# Wireless_IMU_v1_0.net
KiCad netlist of a schematic drawn in EAGLE
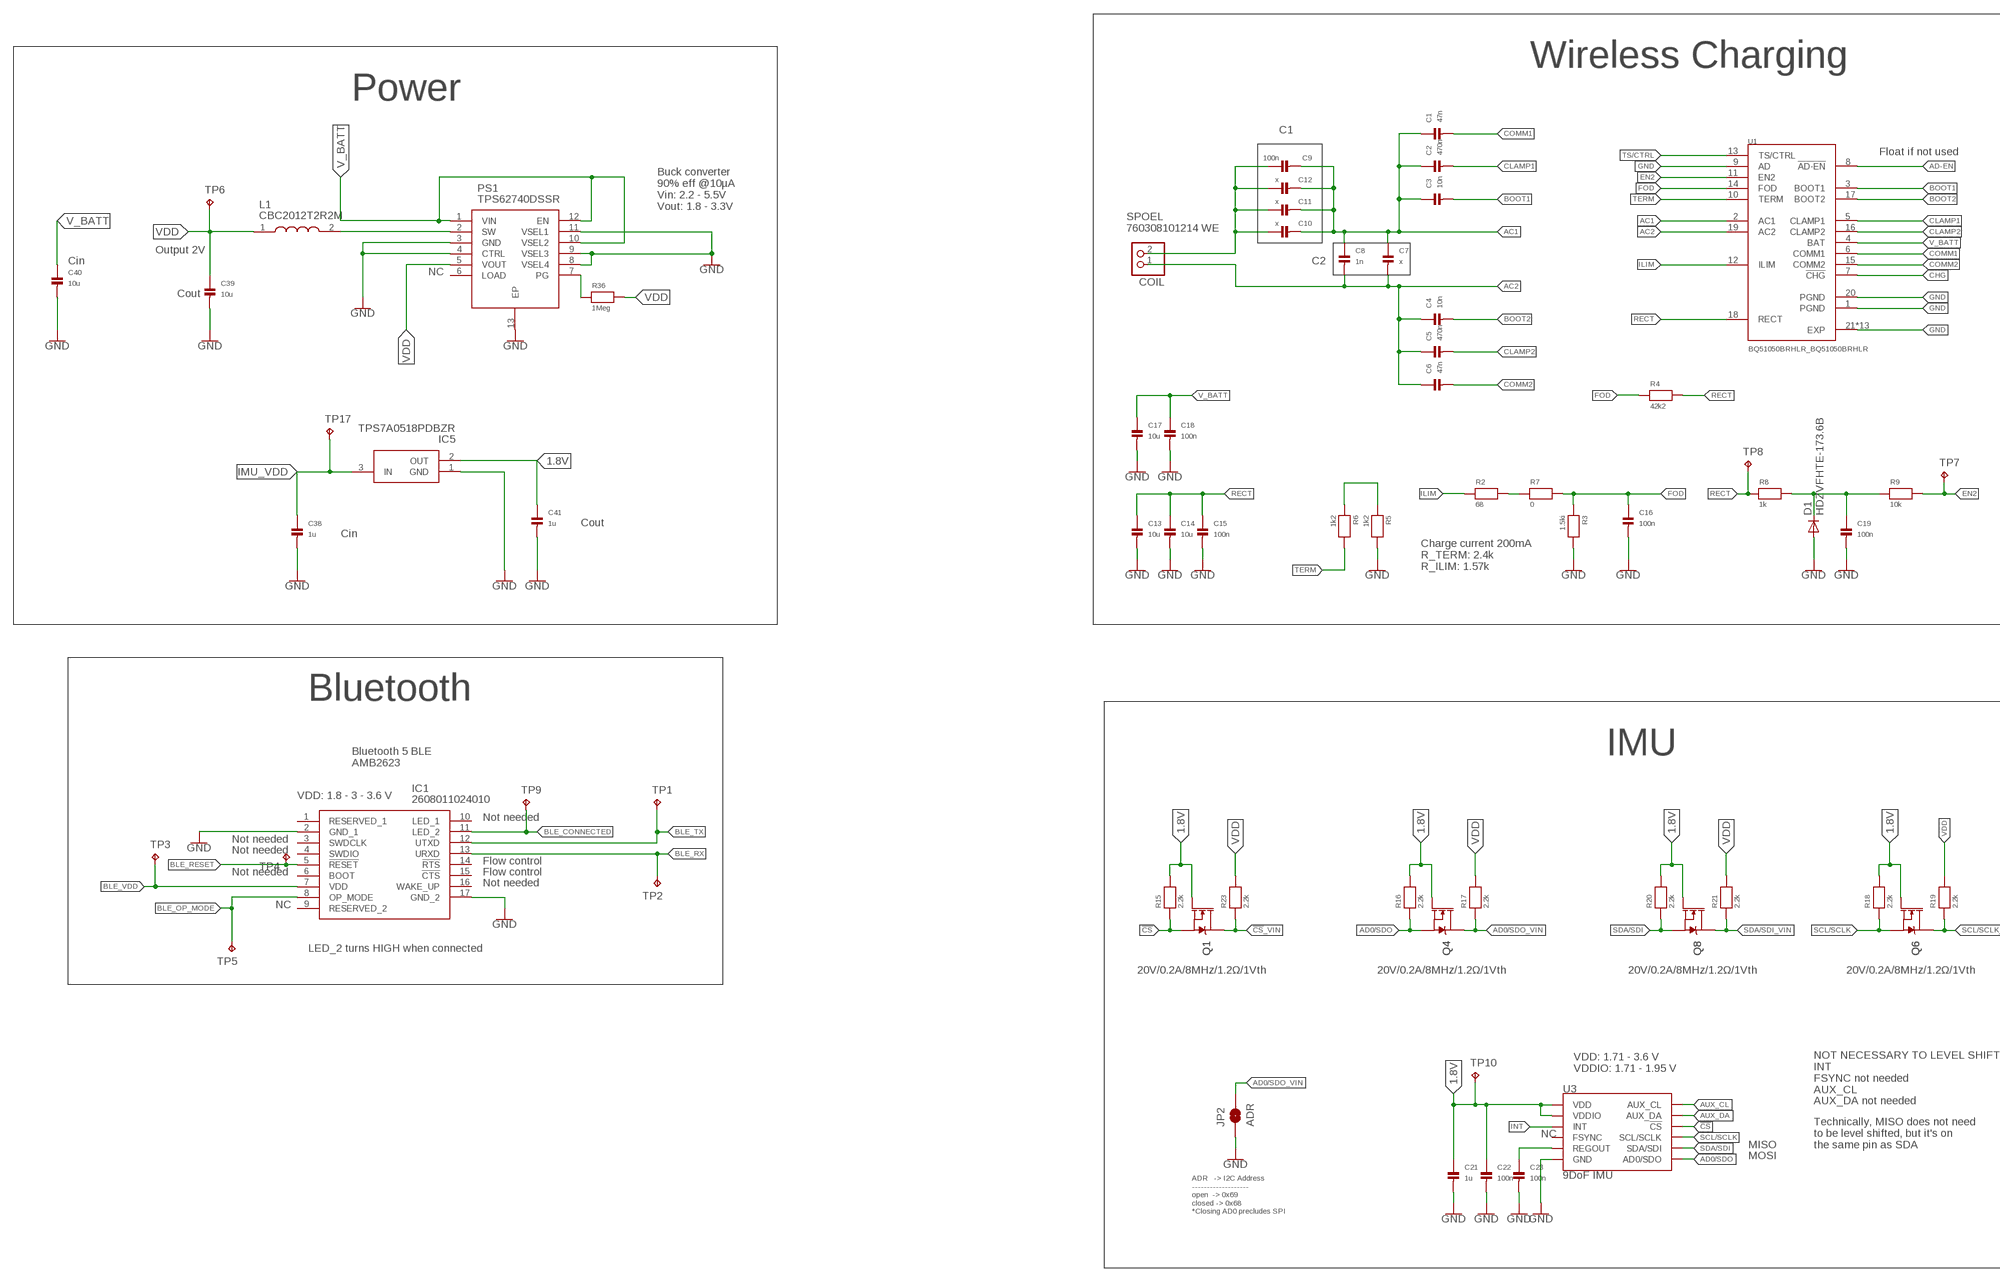
[diagram p0: schematic, sheet 1, part 1 of 2]
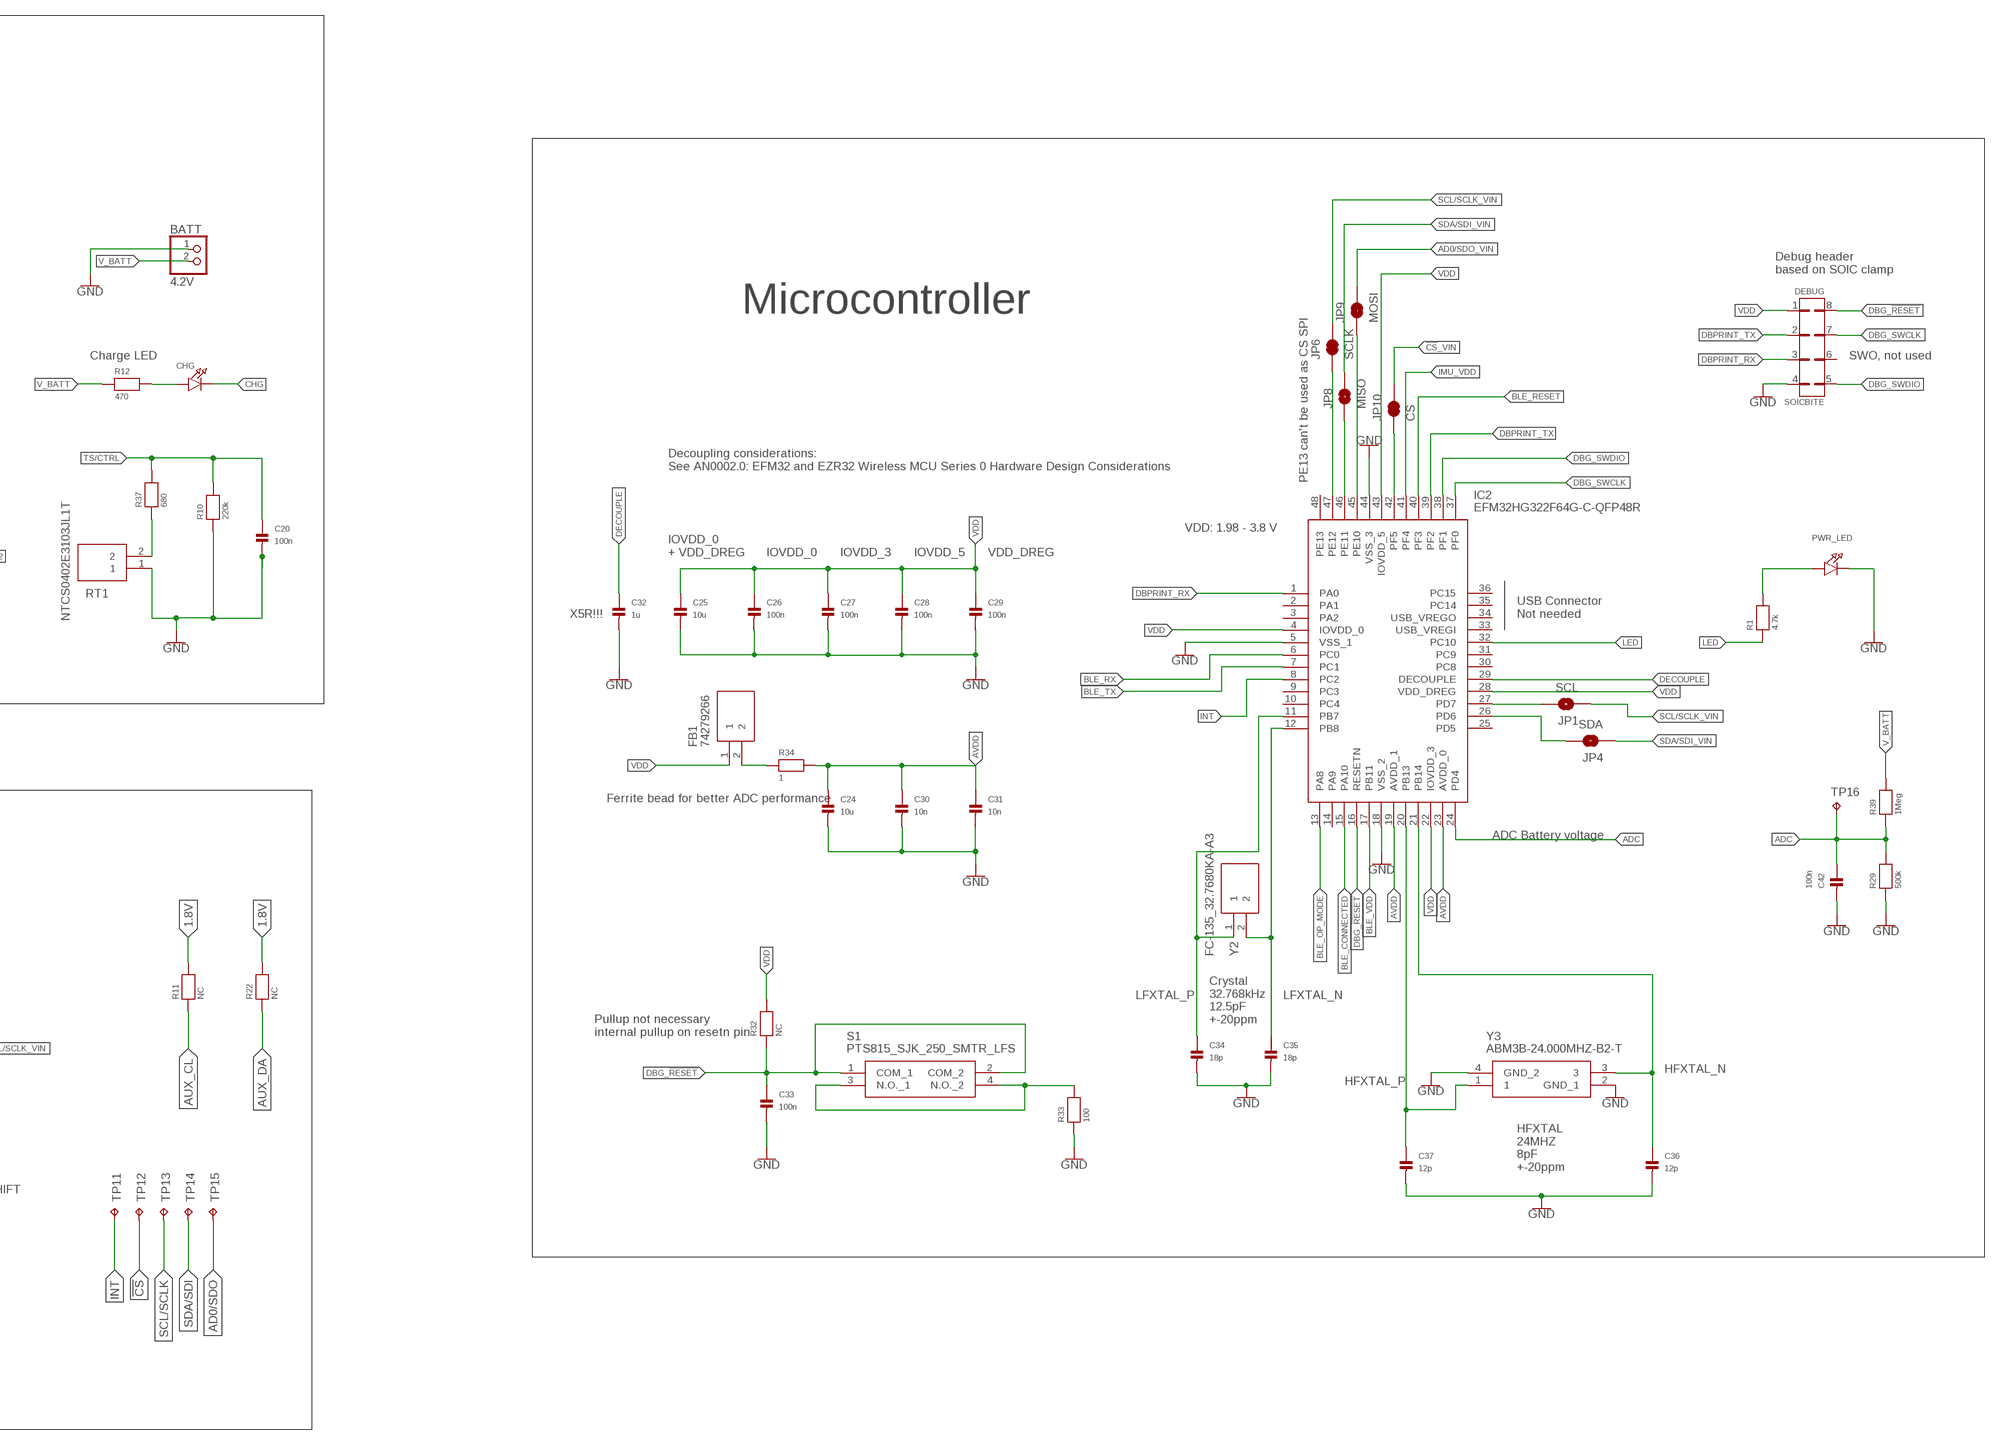
[diagram p1: schematic, sheet 1, part 2 of 2]

(export (version "E")
  (design (tool "Eeschema 10.0.6"))
  (components
    (comp (ref "BATT")
      (value "4.2V")
      (footprint "eagle-import:1X02")
      (libsource (lib "eagle-import") (part "pinhead_325_PINHD-1X2"))
    )
    (comp (ref "C1")
      (value "47n")
      (footprint "eagle-import:0603")
      (libsource (lib "eagle-import") (part "CAP_CERAMIC0603"))
    )
    (comp (ref "C2")
      (value "470n")
      (footprint "eagle-import:0603")
      (libsource (lib "eagle-import") (part "CAP_CERAMIC0603"))
    )
    (comp (ref "C3")
      (value "10n")
      (footprint "eagle-import:0603")
      (libsource (lib "eagle-import") (part "CAP_CERAMIC0603"))
    )
    (comp (ref "C4")
      (value "10n")
      (footprint "eagle-import:0603")
      (libsource (lib "eagle-import") (part "CAP_CERAMIC0603"))
    )
    (comp (ref "C5")
      (value "470n")
      (footprint "eagle-import:0603")
      (libsource (lib "eagle-import") (part "CAP_CERAMIC0603"))
    )
    (comp (ref "C6")
      (value "47n")
      (footprint "eagle-import:0603")
      (libsource (lib "eagle-import") (part "CAP_CERAMIC0603"))
    )
    (comp (ref "C7")
      (value "x")
      (footprint "eagle-import:0603")
      (libsource (lib "eagle-import") (part "CAP_CERAMIC0603"))
    )
    (comp (ref "C8")
      (value "1n")
      (footprint "eagle-import:0603")
      (libsource (lib "eagle-import") (part "CAP_CERAMIC0603"))
    )
    (comp (ref "C9")
      (value "100n")
      (footprint "eagle-import:0603")
      (libsource (lib "eagle-import") (part "CAP_CERAMIC0603"))
    )
    (comp (ref "C10")
      (value "x")
      (footprint "eagle-import:0603")
      (libsource (lib "eagle-import") (part "CAP_CERAMIC0603"))
    )
    (comp (ref "C11")
      (value "x")
      (footprint "eagle-import:0603")
      (libsource (lib "eagle-import") (part "CAP_CERAMIC0603"))
    )
    (comp (ref "C12")
      (value "x")
      (footprint "eagle-import:0603")
      (libsource (lib "eagle-import") (part "CAP_CERAMIC0603"))
    )
    (comp (ref "C13")
      (value "10u")
      (footprint "eagle-import:0603")
      (libsource (lib "eagle-import") (part "CAP_CERAMIC0603"))
    )
    (comp (ref "C14")
      (value "10u")
      (footprint "eagle-import:0603")
      (libsource (lib "eagle-import") (part "CAP_CERAMIC0603"))
    )
    (comp (ref "C15")
      (value "100n")
      (footprint "eagle-import:0603")
      (libsource (lib "eagle-import") (part "CAP_CERAMIC0603"))
    )
    (comp (ref "C16")
      (value "100n")
      (footprint "eagle-import:0603")
      (libsource (lib "eagle-import") (part "CAP_CERAMIC0603"))
    )
    (comp (ref "C17")
      (value "10u")
      (footprint "eagle-import:0603")
      (libsource (lib "eagle-import") (part "CAP_CERAMIC0603"))
    )
    (comp (ref "C18")
      (value "100n")
      (footprint "eagle-import:0603")
      (libsource (lib "eagle-import") (part "CAP_CERAMIC0603"))
    )
    (comp (ref "C19")
      (value "100n")
      (footprint "eagle-import:0603")
      (libsource (lib "eagle-import") (part "CAP_CERAMIC0603"))
    )
    (comp (ref "C20")
      (value "100n")
      (footprint "eagle-import:0603")
      (libsource (lib "eagle-import") (part "CAP_CERAMIC0603"))
    )
    (comp (ref "C21")
      (value "1u")
      (footprint "eagle-import:0603")
      (libsource (lib "eagle-import") (part "CAP_CERAMIC0603"))
    )
    (comp (ref "C22")
      (value "100n")
      (footprint "eagle-import:0603")
      (libsource (lib "eagle-import") (part "CAP_CERAMIC0603"))
    )
    (comp (ref "C23")
      (value "100n")
      (footprint "eagle-import:0603")
      (libsource (lib "eagle-import") (part "CAP_CERAMIC0603"))
    )
    (comp (ref "C24")
      (value "10u")
      (footprint "eagle-import:0603")
      (libsource (lib "eagle-import") (part "CAP_CERAMIC0603"))
    )
    (comp (ref "C25")
      (value "10u")
      (footprint "eagle-import:0603")
      (libsource (lib "eagle-import") (part "CAP_CERAMIC0603"))
    )
    (comp (ref "C26")
      (value "100n")
      (footprint "eagle-import:0603")
      (libsource (lib "eagle-import") (part "CAP_CERAMIC0603"))
    )
    (comp (ref "C27")
      (value "100n")
      (footprint "eagle-import:0603")
      (libsource (lib "eagle-import") (part "CAP_CERAMIC0603"))
    )
    (comp (ref "C28")
      (value "100n")
      (footprint "eagle-import:0603")
      (libsource (lib "eagle-import") (part "CAP_CERAMIC0603"))
    )
    (comp (ref "C29")
      (value "100n")
      (footprint "eagle-import:0603")
      (libsource (lib "eagle-import") (part "CAP_CERAMIC0603"))
    )
    (comp (ref "C30")
      (value "10n")
      (footprint "eagle-import:0603")
      (libsource (lib "eagle-import") (part "CAP_CERAMIC0603"))
    )
    (comp (ref "C31")
      (value "10n")
      (footprint "eagle-import:0603")
      (libsource (lib "eagle-import") (part "CAP_CERAMIC0603"))
    )
    (comp (ref "C32")
      (value "1u")
      (footprint "eagle-import:0603")
      (libsource (lib "eagle-import") (part "CAP_CERAMIC0603"))
    )
    (comp (ref "C33")
      (value "100n")
      (footprint "eagle-import:0603")
      (libsource (lib "eagle-import") (part "CAP_CERAMIC0603"))
    )
    (comp (ref "C34")
      (value "18p")
      (footprint "eagle-import:0603")
      (libsource (lib "eagle-import") (part "CAP_CERAMIC0603"))
    )
    (comp (ref "C35")
      (value "18p")
      (footprint "eagle-import:0603")
      (libsource (lib "eagle-import") (part "CAP_CERAMIC0603"))
    )
    (comp (ref "C36")
      (value "12p")
      (footprint "eagle-import:0603")
      (libsource (lib "eagle-import") (part "CAP_CERAMIC0603"))
    )
    (comp (ref "C37")
      (value "12p")
      (footprint "eagle-import:0603")
      (libsource (lib "eagle-import") (part "CAP_CERAMIC0603"))
    )
    (comp (ref "C38")
      (value "1u")
      (footprint "eagle-import:0603")
      (libsource (lib "eagle-import") (part "CAP_CERAMIC0603"))
    )
    (comp (ref "C39")
      (value "10u")
      (footprint "eagle-import:0603")
      (libsource (lib "eagle-import") (part "CAP_CERAMIC0603"))
    )
    (comp (ref "C40")
      (value "10u")
      (footprint "eagle-import:0603")
      (libsource (lib "eagle-import") (part "CAP_CERAMIC0603"))
    )
    (comp (ref "C41")
      (value "1u")
      (footprint "eagle-import:0603")
      (libsource (lib "eagle-import") (part "CAP_CERAMIC0603"))
    )
    (comp (ref "C42")
      (value "100n")
      (footprint "eagle-import:0603")
      (libsource (lib "eagle-import") (part "CAP_CERAMIC0603"))
    )
    (comp (ref "CHG")
      (value "LED0805")
      (footprint "eagle-import:CHIPLED_0805")
      (libsource (lib "eagle-import") (part "LED0805"))
    )
    (comp (ref "COIL")
      (value "PINHD-1X2")
      (footprint "eagle-import:1X02")
      (libsource (lib "eagle-import") (part "PINHD-1X2"))
    )
    (comp (ref "D1")
      (value "HDZVFHTE-173.6B")
      (footprint "eagle-import:SOD323-W")
      (libsource (lib "eagle-import") (part "DIODE-SOD323-W"))
    )
    (comp (ref "DEBUG")
      (value "SOICBITE")
      (footprint "eagle-import:SOICBITE")
      (libsource (lib "eagle-import") (part "SOICBITE"))
    )
    (comp (ref "FB1")
      (value "74279266")
      (footprint "eagle-import:BEADC1608X100N")
      (fields (field (name "MOUSER_PART_NUMBER") "710-74279266"))
      (libsource (lib "eagle-import") (part "74279266"))
    )
    (comp (ref "IC1")
      (value "2608011024010")
      (footprint "eagle-import:2608011024010")
      (fields (field (name "MOUSER_PART_NUMBER") "710-2608011024010"))
      (libsource (lib "eagle-import") (part "2608011024010"))
    )
    (comp (ref "IC2")
      (value "EFM32HG322F64G-C-QFP48R")
      (footprint "eagle-import:QFP50P900X900X120-48N")
      (fields (field (name "MOUSER_PART_NUMBER") "634-HG322F64GCQFP48R"))
      (libsource (lib "eagle-import") (part "EFM32HG322F64G-C-QFP48R"))
    )
    (comp (ref "IC5")
      (value "TPS7A0518PDBZR")
      (footprint "eagle-import:SOT95P237X112-3N")
      (fields (field (name "MOUSER_PART_NUMBER") "595-TPS7A0518PDBZR"))
      (libsource (lib "eagle-import") (part "TPS7A0518PDBZR"))
    )
    (comp (ref "JP1")
      (value "SCL")
      (footprint "eagle-import:SMT-JUMPER_2_NO_SILK")
      (libsource (lib "eagle-import") (part "JUMPER-SMT_2_NO_SILK"))
    )
    (comp (ref "JP2")
      (value "ADR")
      (footprint "eagle-import:SMT-JUMPER_2_NO_SILK")
      (libsource (lib "eagle-import") (part "JUMPER-SMT_2_NO_SILK"))
    )
    (comp (ref "JP4")
      (value "SDA")
      (footprint "eagle-import:SMT-JUMPER_2_NO_SILK")
      (libsource (lib "eagle-import") (part "JUMPER-SMT_2_NO_SILK"))
    )
    (comp (ref "JP6")
      (value "SCLK")
      (footprint "eagle-import:SMT-JUMPER_2_NC_TRACE_SILK")
      (libsource (lib "eagle-import") (part "JUMPER-SMT_2_NC_TRACE_SILK"))
    )
    (comp (ref "JP8")
      (value "MISO")
      (footprint "eagle-import:SMT-JUMPER_2_NC_TRACE_SILK")
      (libsource (lib "eagle-import") (part "JUMPER-SMT_2_NC_TRACE_SILK"))
    )
    (comp (ref "JP9")
      (value "MOSI")
      (footprint "eagle-import:SMT-JUMPER_2_NC_TRACE_SILK")
      (libsource (lib "eagle-import") (part "JUMPER-SMT_2_NC_TRACE_SILK"))
    )
    (comp (ref "JP10")
      (value "CS")
      (footprint "eagle-import:SMT-JUMPER_2_NC_TRACE_SILK")
      (libsource (lib "eagle-import") (part "JUMPER-SMT_2_NC_TRACE_SILK"))
    )
    (comp (ref "L1")
      (value "CBC2012T2R2M")
      (footprint "eagle-import:INDC2012X145N")
      (fields (field (name "MOUSER_PART_NUMBER") "963-CBC2012T2R2M"))
      (libsource (lib "eagle-import") (part "CBC2012T2R2M"))
    )
    (comp (ref "PS1")
      (value "TPS62740DSSR")
      (footprint "eagle-import:SON50P200X300X80-13N")
      (fields (field (name "MOUSER_PART_NUMBER") "595-TPS62740DSSR"))
      (libsource (lib "eagle-import") (part "TPS62740DSSR"))
    )
    (comp (ref "PWR_LED")
      (value "LED0805")
      (footprint "eagle-import:CHIPLED_0805")
      (libsource (lib "eagle-import") (part "LED0805"))
    )
    (comp (ref "Q1")
      (value "20V/0.2A/8MHz/1.2Ω/1Vth")
      (footprint "eagle-import:SOT-416FL")
      (libsource (lib "eagle-import") (part "MOSFET-NCH-RE1C002UN"))
    )
    (comp (ref "Q4")
      (value "20V/0.2A/8MHz/1.2Ω/1Vth")
      (footprint "eagle-import:SOT-416FL")
      (libsource (lib "eagle-import") (part "MOSFET-NCH-RE1C002UN"))
    )
    (comp (ref "Q6")
      (value "20V/0.2A/8MHz/1.2Ω/1Vth")
      (footprint "eagle-import:SOT-416FL")
      (libsource (lib "eagle-import") (part "MOSFET-NCH-RE1C002UN"))
    )
    (comp (ref "Q8")
      (value "20V/0.2A/8MHz/1.2Ω/1Vth")
      (footprint "eagle-import:SOT-416FL")
      (libsource (lib "eagle-import") (part "MOSFET-NCH-RE1C002UN"))
    )
    (comp (ref "R1")
      (value "4.7k")
      (footprint "eagle-import:0603")
      (libsource (lib "eagle-import") (part "RESISTOR0603"))
    )
    (comp (ref "R2")
      (value "68")
      (footprint "eagle-import:0603")
      (libsource (lib "eagle-import") (part "RESISTOR0603"))
    )
    (comp (ref "R3")
      (value "1.5ki")
      (footprint "eagle-import:0603")
      (libsource (lib "eagle-import") (part "RESISTOR0603"))
    )
    (comp (ref "R4")
      (value "42k2")
      (footprint "eagle-import:0603")
      (libsource (lib "eagle-import") (part "RESISTOR0603"))
    )
    (comp (ref "R5")
      (value "1k2")
      (footprint "eagle-import:0603")
      (libsource (lib "eagle-import") (part "RESISTOR0603"))
    )
    (comp (ref "R6")
      (value "1k2")
      (footprint "eagle-import:0603")
      (libsource (lib "eagle-import") (part "RESISTOR0603"))
    )
    (comp (ref "R7")
      (value "0")
      (footprint "eagle-import:0603")
      (libsource (lib "eagle-import") (part "RESISTOR0603"))
    )
    (comp (ref "R8")
      (value "1k")
      (footprint "eagle-import:0603")
      (libsource (lib "eagle-import") (part "RESISTOR0603"))
    )
    (comp (ref "R9")
      (value "10k")
      (footprint "eagle-import:0603")
      (libsource (lib "eagle-import") (part "RESISTOR0603"))
    )
    (comp (ref "R10")
      (value "220k")
      (footprint "eagle-import:0603")
      (libsource (lib "eagle-import") (part "RESISTOR0603"))
    )
    (comp (ref "R11")
      (value "NC")
      (footprint "eagle-import:0603")
      (libsource (lib "eagle-import") (part "RESISTOR0603"))
    )
    (comp (ref "R12")
      (value "470")
      (footprint "eagle-import:0603")
      (libsource (lib "eagle-import") (part "RESISTOR0603"))
    )
    (comp (ref "R15")
      (value "2.2k")
      (footprint "eagle-import:0603")
      (libsource (lib "eagle-import") (part "RESISTOR0603"))
    )
    (comp (ref "R16")
      (value "2.2k")
      (footprint "eagle-import:0603")
      (libsource (lib "eagle-import") (part "RESISTOR0603"))
    )
    (comp (ref "R17")
      (value "2.2k")
      (footprint "eagle-import:0603")
      (libsource (lib "eagle-import") (part "RESISTOR0603"))
    )
    (comp (ref "R18")
      (value "2.2k")
      (footprint "eagle-import:0603")
      (libsource (lib "eagle-import") (part "RESISTOR0603"))
    )
    (comp (ref "R19")
      (value "2.2k")
      (footprint "eagle-import:0603")
      (libsource (lib "eagle-import") (part "RESISTOR0603"))
    )
    (comp (ref "R20")
      (value "2.2k")
      (footprint "eagle-import:0603")
      (libsource (lib "eagle-import") (part "RESISTOR0603"))
    )
    (comp (ref "R21")
      (value "2.2k")
      (footprint "eagle-import:0603")
      (libsource (lib "eagle-import") (part "RESISTOR0603"))
    )
    (comp (ref "R22")
      (value "NC")
      (footprint "eagle-import:0603")
      (libsource (lib "eagle-import") (part "RESISTOR0603"))
    )
    (comp (ref "R23")
      (value "2.2k")
      (footprint "eagle-import:0603")
      (libsource (lib "eagle-import") (part "RESISTOR0603"))
    )
    (comp (ref "R29")
      (value "500k")
      (footprint "eagle-import:0603")
      (libsource (lib "eagle-import") (part "RESISTOR0603"))
    )
    (comp (ref "R32")
      (value "NC")
      (footprint "eagle-import:0603")
      (libsource (lib "eagle-import") (part "RESISTOR0603"))
    )
    (comp (ref "R33")
      (value "100")
      (footprint "eagle-import:0603")
      (libsource (lib "eagle-import") (part "RESISTOR0603"))
    )
    (comp (ref "R34")
      (value "1")
      (footprint "eagle-import:0603")
      (libsource (lib "eagle-import") (part "RESISTOR0603"))
    )
    (comp (ref "R36")
      (value "1Meg")
      (footprint "eagle-import:0603")
      (libsource (lib "eagle-import") (part "RESISTOR0603"))
    )
    (comp (ref "R37")
      (value "680")
      (footprint "eagle-import:0603")
      (libsource (lib "eagle-import") (part "RESISTOR0603"))
    )
    (comp (ref "R39")
      (value "1Meg")
      (footprint "eagle-import:0603")
      (libsource (lib "eagle-import") (part "RESISTOR0603"))
    )
    (comp (ref "RT1")
      (value "NTCS0402E3103JL1T")
      (footprint "eagle-import:CAPC1005X65N")
      (fields (field (name "MOUSER_PART_NUMBER") "594-NTCS402E3103JL1T"))
      (libsource (lib "eagle-import") (part "NTCS0402E3103JL1T"))
    )
    (comp (ref "S1")
      (value "PTS815_SJK_250_SMTR_LFS")
      (footprint "eagle-import:PTS815SJK250SMTRLFS")
      (fields
        (field (name "MANUFACTURER_PART_NUMBER") "PTS815 SJK 250 SMTR LFS")
        (field (name "MOUSER_PART_NUMBER") "611-PTS815SJK250SMTR")
      )
      (libsource (lib "eagle-import") (part "PTS815_SJK_250_SMTR_LFS"))
    )
    (comp (ref "TP1")
      (value "TPTP10R")
      (footprint "eagle-import:TP10R")
      (libsource (lib "eagle-import") (part "TPTP10R"))
    )
    (comp (ref "TP2")
      (value "TPTP10R")
      (footprint "eagle-import:TP10R")
      (libsource (lib "eagle-import") (part "TPTP10R"))
    )
    (comp (ref "TP3")
      (value "TPTP10R")
      (footprint "eagle-import:TP10R")
      (libsource (lib "eagle-import") (part "TPTP10R"))
    )
    (comp (ref "TP4")
      (value "TPTP10R")
      (footprint "eagle-import:TP10R")
      (libsource (lib "eagle-import") (part "TPTP10R"))
    )
    (comp (ref "TP5")
      (value "TPTP10R")
      (footprint "eagle-import:TP10R")
      (libsource (lib "eagle-import") (part "TPTP10R"))
    )
    (comp (ref "TP6")
      (value "TPTP10R")
      (footprint "eagle-import:TP10R")
      (libsource (lib "eagle-import") (part "TPTP10R"))
    )
    (comp (ref "TP7")
      (value "TPTP10R")
      (footprint "eagle-import:TP10R")
      (libsource (lib "eagle-import") (part "TPTP10R"))
    )
    (comp (ref "TP8")
      (value "TPTP10R")
      (footprint "eagle-import:TP10R")
      (libsource (lib "eagle-import") (part "TPTP10R"))
    )
    (comp (ref "TP9")
      (value "TPTP10R")
      (footprint "eagle-import:TP10R")
      (libsource (lib "eagle-import") (part "TPTP10R"))
    )
    (comp (ref "TP10")
      (value "TPTP10R")
      (footprint "eagle-import:TP10R")
      (libsource (lib "eagle-import") (part "TPTP10R"))
    )
    (comp (ref "TP11")
      (value "TPTP10R")
      (footprint "eagle-import:TP10R")
      (libsource (lib "eagle-import") (part "TPTP10R"))
    )
    (comp (ref "TP12")
      (value "TPTP10R")
      (footprint "eagle-import:TP10R")
      (libsource (lib "eagle-import") (part "TPTP10R"))
    )
    (comp (ref "TP13")
      (value "TPTP10R")
      (footprint "eagle-import:TP10R")
      (libsource (lib "eagle-import") (part "TPTP10R"))
    )
    (comp (ref "TP14")
      (value "TPTP10R")
      (footprint "eagle-import:TP10R")
      (libsource (lib "eagle-import") (part "TPTP10R"))
    )
    (comp (ref "TP15")
      (value "TPTP10R")
      (footprint "eagle-import:TP10R")
      (libsource (lib "eagle-import") (part "TPTP10R"))
    )
    (comp (ref "TP16")
      (value "TPTP10R")
      (footprint "eagle-import:TP10R")
      (libsource (lib "eagle-import") (part "TPTP10R"))
    )
    (comp (ref "TP17")
      (value "TPTP10R")
      (footprint "eagle-import:TP10R")
      (libsource (lib "eagle-import") (part "TPTP10R"))
    )
    (comp (ref "U1")
      (value "BQ51050BRHLR_BQ51050BRHLR")
      (footprint "eagle-import:BQ51050BRHLR_QFN50P450X350X100-21N")
      (fields (field (name "MF") "Texas Instruments") (field (name "MP") "BQ51050BRHLR"))
      (libsource (lib "eagle-import") (part "BQ51050BRHLR_BQ51050BRHLR"))
    )
    (comp (ref "U3")
      (value "9DoF IMU")
      (footprint "eagle-import:SPARKFUN-SENSORS_QFN24-3X3")
      (libsource (lib "eagle-import") (part "SPARKFUN-SENSORS_ICM-20948"))
    )
    (comp (ref "Y2")
      (value "FC-135_32.7680KA-A3")
      (footprint "eagle-import:FC135327680KAAG0")
      (fields
        (field (name "MANUFACTURER_PART_NUMBER") "FC-135 32.7680KA-A3")
        (field (name "MOUSER_PART_NUMBER") "732-FC135-32.76KAA3")
      )
      (libsource (lib "eagle-import") (part "FC-135_32.7680KA-A3"))
    )
    (comp (ref "Y3")
      (value "ABM3B-24.000MHZ-B2-T")
      (footprint "eagle-import:ABM3B8000MHZ101UT")
      (fields (field (name "MOUSER_PART_NUMBER") "815-ABM3B-24-B2"))
      (libsource (lib "eagle-import") (part "ABM3B-24.000MHZ-B2-T"))
    )
  )
  (nets
    (net (code "1") (name "/DBG_~{RESET}") (class "Default")
      (node (ref "C33") (pin "1") (pinfunction "P$1_1") (pintype "passive"))
      (node (ref "DEBUG") (pin "8") (pinfunction "P$8_8") (pintype "passive"))
      (node (ref "IC2") (pin "16") (pinfunction "RESETN_16") (pintype "bidirectional"))
      (node (ref "R32") (pin "1") (pinfunction "1_1") (pintype "passive"))
      (node (ref "S1") (pin "1") (pinfunction "COM_1_1") (pintype "bidirectional"))
      (node (ref "S1") (pin "2") (pinfunction "COM_2_2") (pintype "bidirectional"))
    )
    (net (code "2") (name "/~{CS}") (class "Default")
      (node (ref "Q1") (pin "2") (pinfunction "S_2") (pintype "bidirectional"))
      (node (ref "R15") (pin "1") (pinfunction "1_1") (pintype "passive"))
      (node (ref "TP12") (pin "TP") (pinfunction "TP_TP") (pintype "input"))
      (node (ref "U3") (pin "22") (pinfunction "~{CS}_22") (pintype "bidirectional"))
    )
    (net (code "3") (name "/~{CS}_VIN") (class "Default")
      (node (ref "JP10") (pin "2") (pinfunction "2_2") (pintype "passive"))
      (node (ref "Q1") (pin "3") (pinfunction "D_3") (pintype "bidirectional"))
      (node (ref "R23") (pin "1") (pinfunction "1_1") (pintype "passive"))
    )
    (net (code "4") (name "1.8V") (class "Default")
      (node (ref "C21") (pin "1") (pinfunction "P$1_1") (pintype "passive"))
      (node (ref "C22") (pin "1") (pinfunction "P$1_1") (pintype "passive"))
      (node (ref "C41") (pin "1") (pinfunction "P$1_1") (pintype "passive"))
      (node (ref "IC5") (pin "2") (pinfunction "OUT_2") (pintype "bidirectional"))
      (node (ref "Q1") (pin "1") (pinfunction "G_1") (pintype "bidirectional"))
      (node (ref "Q4") (pin "1") (pinfunction "G_1") (pintype "bidirectional"))
      (node (ref "Q6") (pin "1") (pinfunction "G_1") (pintype "bidirectional"))
      (node (ref "Q8") (pin "1") (pinfunction "G_1") (pintype "bidirectional"))
      (node (ref "R11") (pin "2") (pinfunction "2_2") (pintype "passive"))
      (node (ref "R15") (pin "2") (pinfunction "2_2") (pintype "passive"))
      (node (ref "R16") (pin "2") (pinfunction "2_2") (pintype "passive"))
      (node (ref "R18") (pin "2") (pinfunction "2_2") (pintype "passive"))
      (node (ref "R20") (pin "2") (pinfunction "2_2") (pintype "passive"))
      (node (ref "R22") (pin "2") (pinfunction "2_2") (pintype "passive"))
      (node (ref "TP10") (pin "TP") (pinfunction "TP_TP") (pintype "input"))
      (node (ref "U3") (pin "13") (pinfunction "VDD_13") (pintype "bidirectional"))
      (node (ref "U3") (pin "8") (pinfunction "VDDIO_8") (pintype "bidirectional"))
    )
    (net (code "5") (name "AC1") (class "Default")
      (node (ref "C1") (pin "1") (pinfunction "P$1_1") (pintype "passive"))
      (node (ref "C10") (pin "2") (pinfunction "P$2_2") (pintype "passive"))
      (node (ref "C11") (pin "2") (pinfunction "P$2_2") (pintype "passive"))
      (node (ref "C12") (pin "2") (pinfunction "P$2_2") (pintype "passive"))
      (node (ref "C2") (pin "1") (pinfunction "P$1_1") (pintype "passive"))
      (node (ref "C3") (pin "1") (pinfunction "P$1_1") (pintype "passive"))
      (node (ref "C7") (pin "1") (pinfunction "P$1_1") (pintype "passive"))
      (node (ref "C8") (pin "1") (pinfunction "P$1_1") (pintype "passive"))
      (node (ref "C9") (pin "2") (pinfunction "P$2_2") (pintype "passive"))
      (node (ref "U1") (pin "2") (pinfunction "AC1_2") (pintype "input"))
    )
    (net (code "6") (name "AC2") (class "Default")
      (node (ref "C4") (pin "1") (pinfunction "P$1_1") (pintype "passive"))
      (node (ref "C5") (pin "1") (pinfunction "P$1_1") (pintype "passive"))
      (node (ref "C6") (pin "1") (pinfunction "P$1_1") (pintype "passive"))
      (node (ref "C7") (pin "2") (pinfunction "P$2_2") (pintype "passive"))
      (node (ref "C8") (pin "2") (pinfunction "P$2_2") (pintype "passive"))
      (node (ref "COIL") (pin "1") (pinfunction "1_1") (pintype "passive"))
      (node (ref "U1") (pin "19") (pinfunction "AC2_19") (pintype "input"))
    )
    (net (code "7") (name "AD-EN") (class "Default")
      (node (ref "U1") (pin "8") (pinfunction "~{AD-EN}_8") (pintype "output"))
    )
    (net (code "8") (name "AD0{slash}SDO") (class "Default")
      (node (ref "Q4") (pin "2") (pinfunction "S_2") (pintype "bidirectional"))
      (node (ref "R16") (pin "1") (pinfunction "1_1") (pintype "passive"))
      (node (ref "TP15") (pin "TP") (pinfunction "TP_TP") (pintype "input"))
      (node (ref "U3") (pin "9") (pinfunction "AD0/SDO_9") (pintype "bidirectional"))
    )
    (net (code "9") (name "AD0{slash}SDO_VIN") (class "Default")
      (node (ref "JP2") (pin "2") (pinfunction "2_2") (pintype "passive"))
      (node (ref "JP9") (pin "2") (pinfunction "2_2") (pintype "passive"))
      (node (ref "Q4") (pin "3") (pinfunction "D_3") (pintype "bidirectional"))
      (node (ref "R17") (pin "1") (pinfunction "1_1") (pintype "passive"))
    )
    (net (code "10") (name "ADC") (class "Default")
      (node (ref "C42") (pin "1") (pinfunction "P$1_1") (pintype "passive"))
      (node (ref "IC2") (pin "24") (pinfunction "PD4_24") (pintype "bidirectional"))
      (node (ref "R29") (pin "2") (pinfunction "2_2") (pintype "passive"))
      (node (ref "R39") (pin "1") (pinfunction "1_1") (pintype "passive"))
      (node (ref "TP16") (pin "TP") (pinfunction "TP_TP") (pintype "input"))
    )
    (net (code "11") (name "AUX_CL") (class "Default")
      (node (ref "R11") (pin "1") (pinfunction "1_1") (pintype "passive"))
      (node (ref "U3") (pin "7") (pinfunction "AUX_CL_7") (pintype "bidirectional"))
    )
    (net (code "12") (name "AUX_DA") (class "Default")
      (node (ref "R22") (pin "1") (pinfunction "1_1") (pintype "passive"))
      (node (ref "U3") (pin "21") (pinfunction "AUX_DA_21") (pintype "bidirectional"))
    )
    (net (code "13") (name "AVDD") (class "Default")
      (node (ref "C24") (pin "1") (pinfunction "P$1_1") (pintype "passive"))
      (node (ref "C30") (pin "1") (pinfunction "P$1_1") (pintype "passive"))
      (node (ref "C31") (pin "1") (pinfunction "P$1_1") (pintype "passive"))
      (node (ref "IC2") (pin "19") (pinfunction "AVDD_1_19") (pintype "bidirectional"))
      (node (ref "IC2") (pin "23") (pinfunction "AVDD_0_23") (pintype "bidirectional"))
      (node (ref "R34") (pin "2") (pinfunction "2_2") (pintype "passive"))
    )
    (net (code "14") (name "BLE_CONNECTED") (class "Default")
      (node (ref "IC1") (pin "11") (pinfunction "LED_2_11") (pintype "bidirectional"))
      (node (ref "IC2") (pin "15") (pinfunction "PA10_15") (pintype "bidirectional"))
      (node (ref "TP9") (pin "TP") (pinfunction "TP_TP") (pintype "input"))
    )
    (net (code "15") (name "BLE_OP_MODE") (class "Default")
      (node (ref "IC1") (pin "8") (pinfunction "OP_MODE_8") (pintype "bidirectional"))
      (node (ref "IC2") (pin "13") (pinfunction "PA8_13") (pintype "bidirectional"))
      (node (ref "TP5") (pin "TP") (pinfunction "TP_TP") (pintype "input"))
    )
    (net (code "16") (name "BLE_RESET") (class "Default")
      (node (ref "IC1") (pin "5") (pinfunction "~{RESET}_5") (pintype "bidirectional"))
      (node (ref "IC2") (pin "40") (pinfunction "PF3_40") (pintype "bidirectional"))
      (node (ref "TP4") (pin "TP") (pinfunction "TP_TP") (pintype "input"))
    )
    (net (code "17") (name "BLE_RX") (class "Default")
      (node (ref "IC1") (pin "13") (pinfunction "URXD_13") (pintype "bidirectional"))
      (node (ref "IC2") (pin "6") (pinfunction "PC0_6") (pintype "bidirectional"))
      (node (ref "TP2") (pin "TP") (pinfunction "TP_TP") (pintype "input"))
    )
    (net (code "18") (name "BLE_TX") (class "Default")
      (node (ref "IC1") (pin "12") (pinfunction "UTXD_12") (pintype "bidirectional"))
      (node (ref "IC2") (pin "7") (pinfunction "PC1_7") (pintype "bidirectional"))
      (node (ref "TP1") (pin "TP") (pinfunction "TP_TP") (pintype "input"))
    )
    (net (code "19") (name "BLE_VDD") (class "Default")
      (node (ref "IC1") (pin "7") (pinfunction "VDD_7") (pintype "bidirectional"))
      (node (ref "IC2") (pin "17") (pinfunction "PB11_17") (pintype "bidirectional"))
      (node (ref "TP3") (pin "TP") (pinfunction "TP_TP") (pintype "input"))
    )
    (net (code "20") (name "BOOT1") (class "Default")
      (node (ref "C3") (pin "2") (pinfunction "P$2_2") (pintype "passive"))
      (node (ref "U1") (pin "3") (pinfunction "BOOT1_3") (pintype "output"))
    )
    (net (code "21") (name "BOOT2") (class "Default")
      (node (ref "C4") (pin "2") (pinfunction "P$2_2") (pintype "passive"))
      (node (ref "U1") (pin "17") (pinfunction "BOOT2_17") (pintype "output"))
    )
    (net (code "22") (name "CHG") (class "Default")
      (node (ref "CHG") (pin "C") (pinfunction "C_C") (pintype "passive"))
      (node (ref "U1") (pin "7") (pinfunction "~{CHG}_7") (pintype "output"))
    )
    (net (code "23") (name "CLAMP1") (class "Default")
      (node (ref "C2") (pin "2") (pinfunction "P$2_2") (pintype "passive"))
      (node (ref "U1") (pin "5") (pinfunction "CLAMP1_5") (pintype "output"))
    )
    (net (code "24") (name "CLAMP2") (class "Default")
      (node (ref "C5") (pin "2") (pinfunction "P$2_2") (pintype "passive"))
      (node (ref "U1") (pin "16") (pinfunction "CLAMP2_16") (pintype "output"))
    )
    (net (code "25") (name "COMM1") (class "Default")
      (node (ref "C1") (pin "2") (pinfunction "P$2_2") (pintype "passive"))
      (node (ref "U1") (pin "6") (pinfunction "COMM1_6") (pintype "output"))
    )
    (net (code "26") (name "COMM2") (class "Default")
      (node (ref "C6") (pin "2") (pinfunction "P$2_2") (pintype "passive"))
      (node (ref "U1") (pin "15") (pinfunction "COMM2_15") (pintype "output"))
    )
    (net (code "27") (name "DBG_SWCLK") (class "Default")
      (node (ref "DEBUG") (pin "7") (pinfunction "P$7_7") (pintype "passive"))
      (node (ref "IC2") (pin "37") (pinfunction "PF0_37") (pintype "bidirectional"))
    )
    (net (code "28") (name "DBG_SWDIO") (class "Default")
      (node (ref "DEBUG") (pin "5") (pinfunction "P$5_5") (pintype "passive"))
      (node (ref "IC2") (pin "38") (pinfunction "PF1_38") (pintype "bidirectional"))
    )
    (net (code "29") (name "DBPRINT_RX") (class "Default")
      (node (ref "DEBUG") (pin "3") (pinfunction "P$3_3") (pintype "passive"))
      (node (ref "IC2") (pin "1") (pinfunction "PA0_1") (pintype "bidirectional"))
    )
    (net (code "30") (name "DBPRINT_TX") (class "Default")
      (node (ref "DEBUG") (pin "2") (pinfunction "P$2_2") (pintype "passive"))
      (node (ref "IC2") (pin "39") (pinfunction "PF2_39") (pintype "bidirectional"))
    )
    (net (code "31") (name "DECOUPLE") (class "Default")
      (node (ref "C32") (pin "1") (pinfunction "P$1_1") (pintype "passive"))
      (node (ref "IC2") (pin "29") (pinfunction "DECOUPLE_29") (pintype "bidirectional"))
    )
    (net (code "32") (name "EN2") (class "Default")
      (node (ref "R9") (pin "2") (pinfunction "2_2") (pintype "passive"))
      (node (ref "TP7") (pin "TP") (pinfunction "TP_TP") (pintype "input"))
      (node (ref "U1") (pin "11") (pinfunction "EN2_11") (pintype "input"))
    )
    (net (code "33") (name "FOD") (class "Default")
      (node (ref "C16") (pin "1") (pinfunction "P$1_1") (pintype "passive"))
      (node (ref "R3") (pin "1") (pinfunction "1_1") (pintype "passive"))
      (node (ref "R4") (pin "1") (pinfunction "1_1") (pintype "passive"))
      (node (ref "R7") (pin "2") (pinfunction "2_2") (pintype "passive"))
      (node (ref "U1") (pin "14") (pinfunction "FOD_14") (pintype "input"))
    )
    (net (code "34") (name "GND") (class "Default")
      (node (ref "BATT") (pin "1") (pinfunction "1_1") (pintype "passive"))
      (node (ref "C13") (pin "2") (pinfunction "P$2_2") (pintype "passive"))
      (node (ref "C14") (pin "2") (pinfunction "P$2_2") (pintype "passive"))
      (node (ref "C15") (pin "2") (pinfunction "P$2_2") (pintype "passive"))
      (node (ref "C16") (pin "2") (pinfunction "P$2_2") (pintype "passive"))
      (node (ref "C17") (pin "2") (pinfunction "P$2_2") (pintype "passive"))
      (node (ref "C18") (pin "2") (pinfunction "P$2_2") (pintype "passive"))
      (node (ref "C19") (pin "2") (pinfunction "P$2_2") (pintype "passive"))
      (node (ref "C20") (pin "2") (pinfunction "P$2_2") (pintype "passive"))
      (node (ref "C21") (pin "2") (pinfunction "P$2_2") (pintype "passive"))
      (node (ref "C22") (pin "2") (pinfunction "P$2_2") (pintype "passive"))
      (node (ref "C23") (pin "2") (pinfunction "P$2_2") (pintype "passive"))
      (node (ref "C24") (pin "2") (pinfunction "P$2_2") (pintype "passive"))
      (node (ref "C25") (pin "2") (pinfunction "P$2_2") (pintype "passive"))
      (node (ref "C26") (pin "2") (pinfunction "P$2_2") (pintype "passive"))
      (node (ref "C27") (pin "2") (pinfunction "P$2_2") (pintype "passive"))
      (node (ref "C28") (pin "2") (pinfunction "P$2_2") (pintype "passive"))
      (node (ref "C29") (pin "2") (pinfunction "P$2_2") (pintype "passive"))
      (node (ref "C30") (pin "2") (pinfunction "P$2_2") (pintype "passive"))
      (node (ref "C31") (pin "2") (pinfunction "P$2_2") (pintype "passive"))
      (node (ref "C32") (pin "2") (pinfunction "P$2_2") (pintype "passive"))
      (node (ref "C33") (pin "2") (pinfunction "P$2_2") (pintype "passive"))
      (node (ref "C34") (pin "2") (pinfunction "P$2_2") (pintype "passive"))
      (node (ref "C35") (pin "2") (pinfunction "P$2_2") (pintype "passive"))
      (node (ref "C36") (pin "2") (pinfunction "P$2_2") (pintype "passive"))
      (node (ref "C37") (pin "2") (pinfunction "P$2_2") (pintype "passive"))
      (node (ref "C38") (pin "2") (pinfunction "P$2_2") (pintype "passive"))
      (node (ref "C39") (pin "2") (pinfunction "P$2_2") (pintype "passive"))
      (node (ref "C40") (pin "2") (pinfunction "P$2_2") (pintype "passive"))
      (node (ref "C41") (pin "2") (pinfunction "P$2_2") (pintype "passive"))
      (node (ref "C42") (pin "2") (pinfunction "P$2_2") (pintype "passive"))
      (node (ref "D1") (pin "A") (pinfunction "A_A") (pintype "passive"))
      (node (ref "DEBUG") (pin "4") (pinfunction "P$4_4") (pintype "passive"))
      (node (ref "IC1") (pin "17") (pinfunction "GND_2_17") (pintype "bidirectional"))
      (node (ref "IC1") (pin "2") (pinfunction "GND_1_2") (pintype "bidirectional"))
      (node (ref "IC2") (pin "18") (pinfunction "VSS_2_18") (pintype "bidirectional"))
      (node (ref "IC2") (pin "44") (pinfunction "VSS_3_44") (pintype "bidirectional"))
      (node (ref "IC2") (pin "5") (pinfunction "VSS_1_5") (pintype "bidirectional"))
      (node (ref "IC5") (pin "1") (pinfunction "GND_1") (pintype "bidirectional"))
      (node (ref "JP2") (pin "1") (pinfunction "1_1") (pintype "passive"))
      (node (ref "PS1") (pin "11") (pinfunction "VSEL1_11") (pintype "bidirectional"))
      (node (ref "PS1") (pin "13") (pinfunction "EP_13") (pintype "bidirectional"))
      (node (ref "PS1") (pin "3") (pinfunction "GND_3") (pintype "power_in"))
      (node (ref "PS1") (pin "4") (pinfunction "CTRL_4") (pintype "bidirectional"))
      (node (ref "PS1") (pin "8") (pinfunction "VSEL4_8") (pintype "bidirectional"))
      (node (ref "PS1") (pin "9") (pinfunction "VSEL3_9") (pintype "bidirectional"))
      (node (ref "PWR_LED") (pin "C") (pinfunction "C_C") (pintype "passive"))
      (node (ref "R10") (pin "1") (pinfunction "1_1") (pintype "passive"))
      (node (ref "R29") (pin "1") (pinfunction "1_1") (pintype "passive"))
      (node (ref "R3") (pin "2") (pinfunction "2_2") (pintype "passive"))
      (node (ref "R33") (pin "1") (pinfunction "1_1") (pintype "passive"))
      (node (ref "R5") (pin "2") (pinfunction "2_2") (pintype "passive"))
      (node (ref "RT1") (pin "1") (pinfunction "1_1") (pintype "bidirectional"))
      (node (ref "U1") (pin "1") (pinfunction "PGND_1") (pintype "power_in"))
      (node (ref "U1") (pin "20") (pinfunction "PGND_20") (pintype "power_in"))
      (node (ref "U1") (pin "21") (pinfunction "EXP_21") (pintype "power_in"))
      (node (ref "U1") (pin "22") (pinfunction "EXP_22") (pintype "power_in"))
      (node (ref "U1") (pin "23") (pinfunction "EXP_23") (pintype "power_in"))
      (node (ref "U1") (pin "24") (pinfunction "EXP_24") (pintype "power_in"))
      (node (ref "U1") (pin "25") (pinfunction "EXP_25") (pintype "power_in"))
      (node (ref "U1") (pin "26") (pinfunction "EXP_26") (pintype "power_in"))
      (node (ref "U1") (pin "27") (pinfunction "EXP_27") (pintype "power_in"))
      (node (ref "U1") (pin "28") (pinfunction "EXP_28") (pintype "power_in"))
      (node (ref "U1") (pin "29") (pinfunction "EXP_29") (pintype "power_in"))
      (node (ref "U1") (pin "30") (pinfunction "EXP_30") (pintype "power_in"))
      (node (ref "U1") (pin "31") (pinfunction "EXP_31") (pintype "power_in"))
      (node (ref "U1") (pin "32") (pinfunction "EXP_32") (pintype "power_in"))
      (node (ref "U1") (pin "33") (pinfunction "EXP_33") (pintype "power_in"))
      (node (ref "U1") (pin "9") (pinfunction "AD_9") (pintype "input"))
      (node (ref "U3") (pin "18") (pinfunction "GND_18") (pintype "bidirectional"))
      (node (ref "U3") (pin "20") (pinfunction "GND_20") (pintype "bidirectional"))
      (node (ref "Y3") (pin "2") (pinfunction "GND_1_2") (pintype "bidirectional"))
      (node (ref "Y3") (pin "4") (pinfunction "GND_2_4") (pintype "bidirectional"))
    )
    (net (code "35") (name "ILIM") (class "Default")
      (node (ref "R2") (pin "1") (pinfunction "1_1") (pintype "passive"))
      (node (ref "U1") (pin "12") (pinfunction "ILIM_12") (pintype "bidirectional"))
    )
    (net (code "36") (name "IMU_VDD") (class "Default")
      (node (ref "C38") (pin "1") (pinfunction "P$1_1") (pintype "passive"))
      (node (ref "IC2") (pin "41") (pinfunction "PF4_41") (pintype "bidirectional"))
      (node (ref "IC5") (pin "3") (pinfunction "IN_3") (pintype "bidirectional"))
      (node (ref "TP17") (pin "TP") (pinfunction "TP_TP") (pintype "input"))
    )
    (net (code "37") (name "INT") (class "Default")
      (node (ref "IC2") (pin "8") (pinfunction "PC2_8") (pintype "bidirectional"))
      (node (ref "TP11") (pin "TP") (pinfunction "TP_TP") (pintype "input"))
      (node (ref "U3") (pin "12") (pinfunction "INT_12") (pintype "bidirectional"))
    )
    (net (code "38") (name "LED") (class "Default")
      (node (ref "IC2") (pin "32") (pinfunction "PC10_32") (pintype "bidirectional"))
      (node (ref "R1") (pin "1") (pinfunction "1_1") (pintype "passive"))
    )
    (net (code "39") (name "Net-(C10-P$1)") (class "Default")
      (node (ref "C10") (pin "1") (pinfunction "P$1_1") (pintype "passive"))
      (node (ref "C11") (pin "1") (pinfunction "P$1_1") (pintype "passive"))
      (node (ref "C12") (pin "1") (pinfunction "P$1_1") (pintype "passive"))
      (node (ref "C9") (pin "1") (pinfunction "P$1_1") (pintype "passive"))
      (node (ref "COIL") (pin "2") (pinfunction "2_2") (pintype "passive"))
    )
    (net (code "40") (name "Net-(C19-P$1)") (class "Default")
      (node (ref "C19") (pin "1") (pinfunction "P$1_1") (pintype "passive"))
      (node (ref "D1") (pin "C") (pinfunction "C_C") (pintype "passive"))
      (node (ref "R8") (pin "2") (pinfunction "2_2") (pintype "passive"))
      (node (ref "R9") (pin "1") (pinfunction "1_1") (pintype "passive"))
    )
    (net (code "41") (name "Net-(C23-P$1)") (class "Default")
      (node (ref "C23") (pin "1") (pinfunction "P$1_1") (pintype "passive"))
      (node (ref "U3") (pin "10") (pinfunction "REGOUT_10") (pintype "bidirectional"))
    )
    (net (code "42") (name "Net-(C34-P$1)") (class "Default")
      (node (ref "C34") (pin "1") (pinfunction "P$1_1") (pintype "passive"))
      (node (ref "IC2") (pin "11") (pinfunction "PB7_11") (pintype "bidirectional"))
      (node (ref "Y2") (pin "1") (pinfunction "1_1") (pintype "bidirectional"))
    )
    (net (code "43") (name "Net-(C35-P$1)") (class "Default")
      (node (ref "C35") (pin "1") (pinfunction "P$1_1") (pintype "passive"))
      (node (ref "IC2") (pin "12") (pinfunction "PB8_12") (pintype "bidirectional"))
      (node (ref "Y2") (pin "2") (pinfunction "2_2") (pintype "bidirectional"))
    )
    (net (code "44") (name "Net-(C36-P$1)") (class "Default")
      (node (ref "C36") (pin "1") (pinfunction "P$1_1") (pintype "passive"))
      (node (ref "IC2") (pin "21") (pinfunction "PB14_21") (pintype "bidirectional"))
      (node (ref "Y3") (pin "3") (pinfunction "3_3") (pintype "bidirectional"))
    )
    (net (code "45") (name "Net-(C37-P$1)") (class "Default")
      (node (ref "C37") (pin "1") (pinfunction "P$1_1") (pintype "passive"))
      (node (ref "IC2") (pin "20") (pinfunction "PB13_20") (pintype "bidirectional"))
      (node (ref "Y3") (pin "1") (pinfunction "1_1") (pintype "bidirectional"))
    )
    (net (code "46") (name "Net-(CHG-PadA)") (class "Default")
      (node (ref "CHG") (pin "A") (pinfunction "A_A") (pintype "passive"))
      (node (ref "R12") (pin "2") (pinfunction "2_2") (pintype "passive"))
    )
    (net (code "47") (name "Net-(FB1-Pad2)") (class "Default")
      (node (ref "FB1") (pin "2") (pinfunction "2_2") (pintype "bidirectional"))
      (node (ref "R34") (pin "1") (pinfunction "1_1") (pintype "passive"))
    )
    (net (code "48") (name "Net-(IC2-PD6)") (class "Default")
      (node (ref "IC2") (pin "26") (pinfunction "PD6_26") (pintype "bidirectional"))
      (node (ref "JP4") (pin "2") (pinfunction "2_2") (pintype "passive"))
    )
    (net (code "49") (name "Net-(IC2-PD7)") (class "Default")
      (node (ref "IC2") (pin "27") (pinfunction "PD7_27") (pintype "bidirectional"))
      (node (ref "JP1") (pin "2") (pinfunction "2_2") (pintype "passive"))
    )
    (net (code "50") (name "Net-(IC2-PE10)") (class "Default")
      (node (ref "IC2") (pin "45") (pinfunction "PE10_45") (pintype "bidirectional"))
      (node (ref "JP9") (pin "1") (pinfunction "1_1") (pintype "passive"))
    )
    (net (code "51") (name "Net-(IC2-PE11)") (class "Default")
      (node (ref "IC2") (pin "46") (pinfunction "PE11_46") (pintype "bidirectional"))
      (node (ref "JP8") (pin "1") (pinfunction "1_1") (pintype "passive"))
    )
    (net (code "52") (name "Net-(IC2-PE12)") (class "Default")
      (node (ref "IC2") (pin "47") (pinfunction "PE12_47") (pintype "bidirectional"))
      (node (ref "JP6") (pin "1") (pinfunction "1_1") (pintype "passive"))
    )
    (net (code "53") (name "Net-(IC2-PF5)") (class "Default")
      (node (ref "IC2") (pin "42") (pinfunction "PF5_42") (pintype "bidirectional"))
      (node (ref "JP10") (pin "1") (pinfunction "1_1") (pintype "passive"))
    )
    (net (code "54") (name "Net-(PS1-PG)") (class "Default")
      (node (ref "PS1") (pin "7") (pinfunction "PG_7") (pintype "bidirectional"))
      (node (ref "R36") (pin "1") (pinfunction "1_1") (pintype "passive"))
    )
    (net (code "55") (name "Net-(PS1-SW)") (class "Default")
      (node (ref "L1") (pin "2") (pinfunction "2_2") (pintype "bidirectional"))
      (node (ref "PS1") (pin "2") (pinfunction "SW_2") (pintype "bidirectional"))
    )
    (net (code "56") (name "Net-(PWR_LED-PadA)") (class "Default")
      (node (ref "PWR_LED") (pin "A") (pinfunction "A_A") (pintype "passive"))
      (node (ref "R1") (pin "2") (pinfunction "2_2") (pintype "passive"))
    )
    (net (code "57") (name "Net-(R2-Pad2)") (class "Default")
      (node (ref "R2") (pin "2") (pinfunction "2_2") (pintype "passive"))
      (node (ref "R7") (pin "1") (pinfunction "1_1") (pintype "passive"))
    )
    (net (code "58") (name "Net-(R5-Pad1)") (class "Default")
      (node (ref "R5") (pin "1") (pinfunction "1_1") (pintype "passive"))
      (node (ref "R6") (pin "1") (pinfunction "1_1") (pintype "passive"))
    )
    (net (code "59") (name "Net-(R37-Pad1)") (class "Default")
      (node (ref "R37") (pin "1") (pinfunction "1_1") (pintype "passive"))
      (node (ref "RT1") (pin "2") (pinfunction "2_2") (pintype "bidirectional"))
    )
    (net (code "60") (name "Net-(S1-N.O._1)") (class "Default")
      (node (ref "R33") (pin "2") (pinfunction "2_2") (pintype "passive"))
      (node (ref "S1") (pin "3") (pinfunction "N.O._1_3") (pintype "bidirectional"))
      (node (ref "S1") (pin "4") (pinfunction "N.O._2_4") (pintype "bidirectional"))
    )
    (net (code "61") (name "RECT") (class "Default")
      (node (ref "C13") (pin "1") (pinfunction "P$1_1") (pintype "passive"))
      (node (ref "C14") (pin "1") (pinfunction "P$1_1") (pintype "passive"))
      (node (ref "C15") (pin "1") (pinfunction "P$1_1") (pintype "passive"))
      (node (ref "R4") (pin "2") (pinfunction "2_2") (pintype "passive"))
      (node (ref "R8") (pin "1") (pinfunction "1_1") (pintype "passive"))
      (node (ref "TP8") (pin "TP") (pinfunction "TP_TP") (pintype "input"))
      (node (ref "U1") (pin "18") (pinfunction "RECT_18") (pintype "passive"))
    )
    (net (code "62") (name "SCL{slash}SCLK") (class "Default")
      (node (ref "Q6") (pin "2") (pinfunction "S_2") (pintype "bidirectional"))
      (node (ref "R18") (pin "1") (pinfunction "1_1") (pintype "passive"))
      (node (ref "TP13") (pin "TP") (pinfunction "TP_TP") (pintype "input"))
      (node (ref "U3") (pin "23") (pinfunction "SCL/SCLK_23") (pintype "bidirectional"))
    )
    (net (code "63") (name "SCL{slash}SCLK_VIN") (class "Default")
      (node (ref "JP1") (pin "1") (pinfunction "1_1") (pintype "passive"))
      (node (ref "JP6") (pin "2") (pinfunction "2_2") (pintype "passive"))
      (node (ref "Q6") (pin "3") (pinfunction "D_3") (pintype "bidirectional"))
      (node (ref "R19") (pin "1") (pinfunction "1_1") (pintype "passive"))
    )
    (net (code "64") (name "SDA{slash}SDI") (class "Default")
      (node (ref "Q8") (pin "2") (pinfunction "S_2") (pintype "bidirectional"))
      (node (ref "R20") (pin "1") (pinfunction "1_1") (pintype "passive"))
      (node (ref "TP14") (pin "TP") (pinfunction "TP_TP") (pintype "input"))
      (node (ref "U3") (pin "24") (pinfunction "SDA/SDI_24") (pintype "bidirectional"))
    )
    (net (code "65") (name "SDA{slash}SDI_VIN") (class "Default")
      (node (ref "JP4") (pin "1") (pinfunction "1_1") (pintype "passive"))
      (node (ref "JP8") (pin "2") (pinfunction "2_2") (pintype "passive"))
      (node (ref "Q8") (pin "3") (pinfunction "D_3") (pintype "bidirectional"))
      (node (ref "R21") (pin "1") (pinfunction "1_1") (pintype "passive"))
    )
    (net (code "66") (name "TERM") (class "Default")
      (node (ref "R6") (pin "2") (pinfunction "2_2") (pintype "passive"))
      (node (ref "U1") (pin "10") (pinfunction "TERM_10") (pintype "input"))
    )
    (net (code "67") (name "TS{slash}CTRL") (class "Default")
      (node (ref "C20") (pin "1") (pinfunction "P$1_1") (pintype "passive"))
      (node (ref "R10") (pin "2") (pinfunction "2_2") (pintype "passive"))
      (node (ref "R37") (pin "2") (pinfunction "2_2") (pintype "passive"))
      (node (ref "U1") (pin "13") (pinfunction "TS/CTRL_13") (pintype "input"))
    )
    (net (code "68") (name "VDD") (class "Default")
      (node (ref "C25") (pin "1") (pinfunction "P$1_1") (pintype "passive"))
      (node (ref "C26") (pin "1") (pinfunction "P$1_1") (pintype "passive"))
      (node (ref "C27") (pin "1") (pinfunction "P$1_1") (pintype "passive"))
      (node (ref "C28") (pin "1") (pinfunction "P$1_1") (pintype "passive"))
      (node (ref "C29") (pin "1") (pinfunction "P$1_1") (pintype "passive"))
      (node (ref "C39") (pin "1") (pinfunction "P$1_1") (pintype "passive"))
      (node (ref "DEBUG") (pin "1") (pinfunction "P$1_1") (pintype "passive"))
      (node (ref "FB1") (pin "1") (pinfunction "1_1") (pintype "bidirectional"))
      (node (ref "IC2") (pin "22") (pinfunction "IOVDD_3_22") (pintype "bidirectional"))
      (node (ref "IC2") (pin "28") (pinfunction "VDD_DREG_28") (pintype "bidirectional"))
      (node (ref "IC2") (pin "4") (pinfunction "IOVDD_0_4") (pintype "bidirectional"))
      (node (ref "IC2") (pin "43") (pinfunction "IOVDD_5_43") (pintype "bidirectional"))
      (node (ref "L1") (pin "1") (pinfunction "1_1") (pintype "bidirectional"))
      (node (ref "PS1") (pin "5") (pinfunction "VOUT_5") (pintype "output"))
      (node (ref "R17") (pin "2") (pinfunction "2_2") (pintype "passive"))
      (node (ref "R19") (pin "2") (pinfunction "2_2") (pintype "passive"))
      (node (ref "R21") (pin "2") (pinfunction "2_2") (pintype "passive"))
      (node (ref "R23") (pin "2") (pinfunction "2_2") (pintype "passive"))
      (node (ref "R32") (pin "2") (pinfunction "2_2") (pintype "passive"))
      (node (ref "R36") (pin "2") (pinfunction "2_2") (pintype "passive"))
      (node (ref "TP6") (pin "TP") (pinfunction "TP_TP") (pintype "input"))
    )
    (net (code "69") (name "V_BATT") (class "Default")
      (node (ref "BATT") (pin "2") (pinfunction "2_2") (pintype "passive"))
      (node (ref "C17") (pin "1") (pinfunction "P$1_1") (pintype "passive"))
      (node (ref "C18") (pin "1") (pinfunction "P$1_1") (pintype "passive"))
      (node (ref "C40") (pin "1") (pinfunction "P$1_1") (pintype "passive"))
      (node (ref "PS1") (pin "1") (pinfunction "VIN_1") (pintype "input"))
      (node (ref "PS1") (pin "10") (pinfunction "VSEL2_10") (pintype "bidirectional"))
      (node (ref "PS1") (pin "12") (pinfunction "EN_12") (pintype "bidirectional"))
      (node (ref "R12") (pin "1") (pinfunction "1_1") (pintype "passive"))
      (node (ref "R39") (pin "2") (pinfunction "2_2") (pintype "passive"))
      (node (ref "U1") (pin "4") (pinfunction "BAT_4") (pintype "output"))
    )
    (net (code "70") (name "unconnected-(DEBUG-P$6-Pad6)") (class "Default")
      (node (ref "DEBUG") (pin "6") (pinfunction "P$6_6") (pintype "passive"))
    )
    (net (code "71") (name "unconnected-(IC1-BOOT-Pad6)") (class "Default")
      (node (ref "IC1") (pin "6") (pinfunction "BOOT_6") (pintype "bidirectional"))
    )
    (net (code "72") (name "unconnected-(IC1-LED_1-Pad10)") (class "Default")
      (node (ref "IC1") (pin "10") (pinfunction "LED_1_10") (pintype "bidirectional"))
    )
    (net (code "73") (name "unconnected-(IC1-RESERVED_1-Pad1)") (class "Default")
      (node (ref "IC1") (pin "1") (pinfunction "RESERVED_1_1") (pintype "bidirectional"))
    )
    (net (code "74") (name "unconnected-(IC1-RESERVED_2-Pad9)") (class "Default")
      (node (ref "IC1") (pin "9") (pinfunction "RESERVED_2_9") (pintype "bidirectional"))
    )
    (net (code "75") (name "unconnected-(IC1-SWDCLK-Pad3)") (class "Default")
      (node (ref "IC1") (pin "3") (pinfunction "SWDCLK_3") (pintype "bidirectional"))
    )
    (net (code "76") (name "unconnected-(IC1-SWDIO-Pad4)") (class "Default")
      (node (ref "IC1") (pin "4") (pinfunction "SWDIO_4") (pintype "bidirectional"))
    )
    (net (code "77") (name "unconnected-(IC1-WAKE_UP-Pad16)") (class "Default")
      (node (ref "IC1") (pin "16") (pinfunction "WAKE_UP_16") (pintype "bidirectional"))
    )
    (net (code "78") (name "unconnected-(IC1-~{CTS}-Pad15)") (class "Default")
      (node (ref "IC1") (pin "15") (pinfunction "~{CTS}_15") (pintype "bidirectional"))
    )
    (net (code "79") (name "unconnected-(IC1-~{RTS}-Pad14)") (class "Default")
      (node (ref "IC1") (pin "14") (pinfunction "~{RTS}_14") (pintype "bidirectional"))
    )
    (net (code "80") (name "unconnected-(IC2-PA1-Pad2)") (class "Default")
      (node (ref "IC2") (pin "2") (pinfunction "PA1_2") (pintype "bidirectional"))
    )
    (net (code "81") (name "unconnected-(IC2-PA2-Pad3)") (class "Default")
      (node (ref "IC2") (pin "3") (pinfunction "PA2_3") (pintype "bidirectional"))
    )
    (net (code "82") (name "unconnected-(IC2-PA9-Pad14)") (class "Default")
      (node (ref "IC2") (pin "14") (pinfunction "PA9_14") (pintype "bidirectional"))
    )
    (net (code "83") (name "unconnected-(IC2-PC3-Pad9)") (class "Default")
      (node (ref "IC2") (pin "9") (pinfunction "PC3_9") (pintype "bidirectional"))
    )
    (net (code "84") (name "unconnected-(IC2-PC4-Pad10)") (class "Default")
      (node (ref "IC2") (pin "10") (pinfunction "PC4_10") (pintype "bidirectional"))
    )
    (net (code "85") (name "unconnected-(IC2-PC8-Pad30)") (class "Default")
      (node (ref "IC2") (pin "30") (pinfunction "PC8_30") (pintype "bidirectional"))
    )
    (net (code "86") (name "unconnected-(IC2-PC9-Pad31)") (class "Default")
      (node (ref "IC2") (pin "31") (pinfunction "PC9_31") (pintype "bidirectional"))
    )
    (net (code "87") (name "unconnected-(IC2-PC14-Pad35)") (class "Default")
      (node (ref "IC2") (pin "35") (pinfunction "PC14_35") (pintype "bidirectional"))
    )
    (net (code "88") (name "unconnected-(IC2-PC15-Pad36)") (class "Default")
      (node (ref "IC2") (pin "36") (pinfunction "PC15_36") (pintype "bidirectional"))
    )
    (net (code "89") (name "unconnected-(IC2-PD5-Pad25)") (class "Default")
      (node (ref "IC2") (pin "25") (pinfunction "PD5_25") (pintype "bidirectional"))
    )
    (net (code "90") (name "unconnected-(IC2-PE13-Pad48)") (class "Default")
      (node (ref "IC2") (pin "48") (pinfunction "PE13_48") (pintype "bidirectional"))
    )
    (net (code "91") (name "unconnected-(IC2-USB_VREGI-Pad33)") (class "Default")
      (node (ref "IC2") (pin "33") (pinfunction "USB_VREGI_33") (pintype "bidirectional"))
    )
    (net (code "92") (name "unconnected-(IC2-USB_VREGO-Pad34)") (class "Default")
      (node (ref "IC2") (pin "34") (pinfunction "USB_VREGO_34") (pintype "bidirectional"))
    )
    (net (code "93") (name "unconnected-(PS1-LOAD-Pad6)") (class "Default")
      (node (ref "PS1") (pin "6") (pinfunction "LOAD_6") (pintype "bidirectional"))
    )
    (net (code "94") (name "unconnected-(U3-FSYNC-Pad11)") (class "Default")
      (node (ref "U3") (pin "11") (pinfunction "FSYNC_11") (pintype "bidirectional"))
    )
  )
)
